# quad_exp_vca_pnl.net
KiCad netlist of a schematic drawn in EAGLE
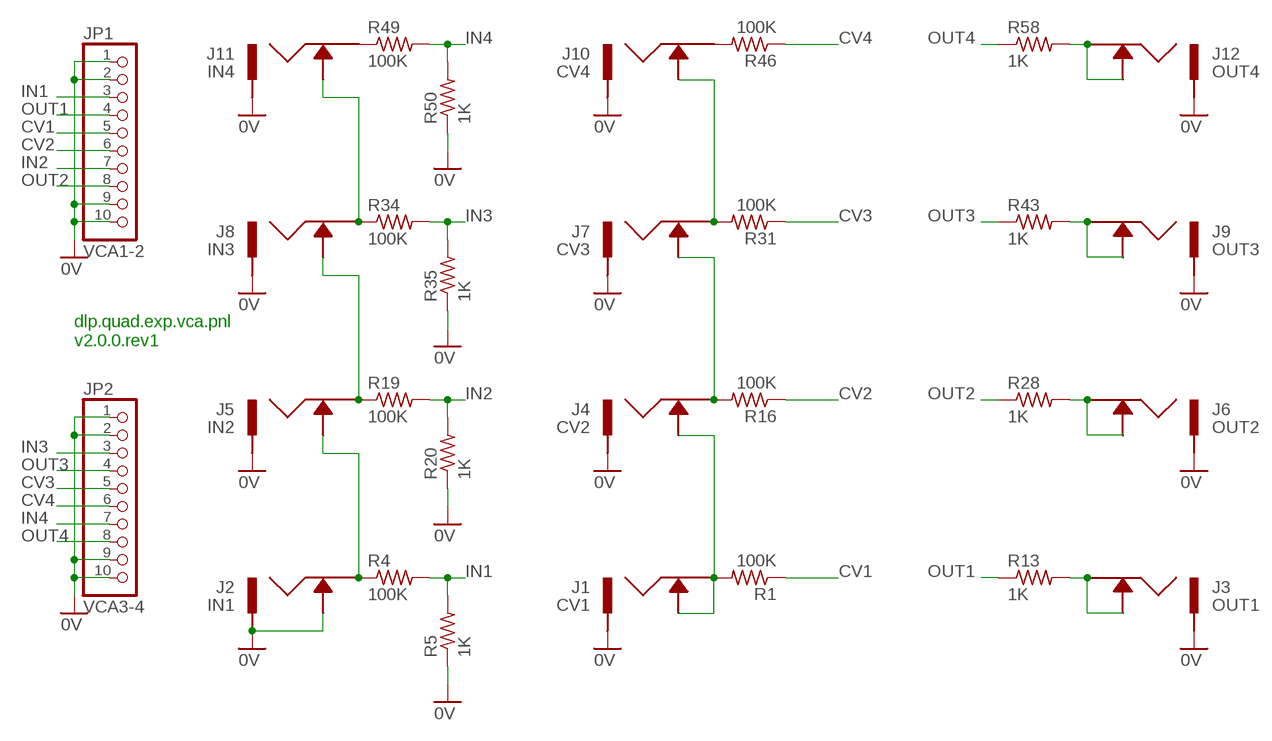
[diagram p0: schematic, sheet 1]

(export (version "E")
  (design (tool "Eeschema 10.0.6"))
  (components
    (comp (ref "J1")
      (value "CV1")
      (footprint "eagle-import:ACJM-MV35-2S")
      (libsource (lib "eagle-import") (part "ACJM-MV35-2S"))
    )
    (comp (ref "J2")
      (value "IN1")
      (footprint "eagle-import:ACJM-MV35-2S")
      (libsource (lib "eagle-import") (part "ACJM-MV35-2S"))
    )
    (comp (ref "J3")
      (value "OUT1")
      (footprint "eagle-import:ACJM-MV35-2S")
      (libsource (lib "eagle-import") (part "ACJM-MV35-2S"))
    )
    (comp (ref "J4")
      (value "CV2")
      (footprint "eagle-import:ACJM-MV35-2S")
      (libsource (lib "eagle-import") (part "ACJM-MV35-2S"))
    )
    (comp (ref "J5")
      (value "IN2")
      (footprint "eagle-import:ACJM-MV35-2S")
      (libsource (lib "eagle-import") (part "ACJM-MV35-2S"))
    )
    (comp (ref "J6")
      (value "OUT2")
      (footprint "eagle-import:ACJM-MV35-2S")
      (libsource (lib "eagle-import") (part "ACJM-MV35-2S"))
    )
    (comp (ref "J7")
      (value "CV3")
      (footprint "eagle-import:ACJM-MV35-2S")
      (libsource (lib "eagle-import") (part "ACJM-MV35-2S"))
    )
    (comp (ref "J8")
      (value "IN3")
      (footprint "eagle-import:ACJM-MV35-2S")
      (libsource (lib "eagle-import") (part "ACJM-MV35-2S"))
    )
    (comp (ref "J9")
      (value "OUT3")
      (footprint "eagle-import:ACJM-MV35-2S")
      (libsource (lib "eagle-import") (part "ACJM-MV35-2S"))
    )
    (comp (ref "J10")
      (value "CV4")
      (footprint "eagle-import:ACJM-MV35-2S")
      (libsource (lib "eagle-import") (part "ACJM-MV35-2S"))
    )
    (comp (ref "J11")
      (value "IN4")
      (footprint "eagle-import:ACJM-MV35-2S")
      (libsource (lib "eagle-import") (part "ACJM-MV35-2S"))
    )
    (comp (ref "J12")
      (value "OUT4")
      (footprint "eagle-import:ACJM-MV35-2S")
      (libsource (lib "eagle-import") (part "ACJM-MV35-2S"))
    )
    (comp (ref "JP1")
      (value "VCA1-2")
      (footprint "eagle-import:1X10")
      (libsource (lib "eagle-import") (part "PINHD-1X10"))
    )
    (comp (ref "JP2")
      (value "VCA3-4")
      (footprint "eagle-import:1X10")
      (libsource (lib "eagle-import") (part "PINHD-1X10"))
    )
    (comp (ref "R1")
      (value "100K")
      (footprint "eagle-import:0207_7")
      (libsource (lib "eagle-import") (part "R-US_0207/7"))
    )
    (comp (ref "R4")
      (value "100K")
      (footprint "eagle-import:0207_7")
      (libsource (lib "eagle-import") (part "R-US_0207/7"))
    )
    (comp (ref "R5")
      (value "1K")
      (footprint "eagle-import:0207_7")
      (libsource (lib "eagle-import") (part "R-US_0207/7"))
    )
    (comp (ref "R13")
      (value "1K")
      (footprint "eagle-import:0207_7")
      (libsource (lib "eagle-import") (part "R-US_0207/7"))
    )
    (comp (ref "R16")
      (value "100K")
      (footprint "eagle-import:0207_7")
      (libsource (lib "eagle-import") (part "R-US_0207/7"))
    )
    (comp (ref "R19")
      (value "100K")
      (footprint "eagle-import:0207_7")
      (libsource (lib "eagle-import") (part "R-US_0207/7"))
    )
    (comp (ref "R20")
      (value "1K")
      (footprint "eagle-import:0207_7")
      (libsource (lib "eagle-import") (part "R-US_0207/7"))
    )
    (comp (ref "R28")
      (value "1K")
      (footprint "eagle-import:0207_7")
      (libsource (lib "eagle-import") (part "R-US_0207/7"))
    )
    (comp (ref "R31")
      (value "100K")
      (footprint "eagle-import:0207_7")
      (libsource (lib "eagle-import") (part "R-US_0207/7"))
    )
    (comp (ref "R34")
      (value "100K")
      (footprint "eagle-import:0207_7")
      (libsource (lib "eagle-import") (part "R-US_0207/7"))
    )
    (comp (ref "R35")
      (value "1K")
      (footprint "eagle-import:0207_7")
      (libsource (lib "eagle-import") (part "R-US_0207/7"))
    )
    (comp (ref "R43")
      (value "1K")
      (footprint "eagle-import:0207_7")
      (libsource (lib "eagle-import") (part "R-US_0207/7"))
    )
    (comp (ref "R46")
      (value "100K")
      (footprint "eagle-import:0207_7")
      (libsource (lib "eagle-import") (part "R-US_0207/7"))
    )
    (comp (ref "R49")
      (value "100K")
      (footprint "eagle-import:0207_7")
      (libsource (lib "eagle-import") (part "R-US_0207/7"))
    )
    (comp (ref "R50")
      (value "1K")
      (footprint "eagle-import:0207_7")
      (libsource (lib "eagle-import") (part "R-US_0207/7"))
    )
    (comp (ref "R58")
      (value "1K")
      (footprint "eagle-import:0207_7")
      (libsource (lib "eagle-import") (part "R-US_0207/7"))
    )
  )
  (nets
    (net (code "1") (name "/CV1") (class "Default")
      (node (ref "JP1") (pin "5") (pinfunction "5_5") (pintype "passive"))
      (node (ref "R1") (pin "1") (pinfunction "1_1") (pintype "passive"))
    )
    (net (code "2") (name "/CV2") (class "Default")
      (node (ref "JP1") (pin "6") (pinfunction "6_6") (pintype "passive"))
      (node (ref "R16") (pin "1") (pinfunction "1_1") (pintype "passive"))
    )
    (net (code "3") (name "/CV3") (class "Default")
      (node (ref "JP2") (pin "5") (pinfunction "5_5") (pintype "passive"))
      (node (ref "R31") (pin "1") (pinfunction "1_1") (pintype "passive"))
    )
    (net (code "4") (name "/CV4") (class "Default")
      (node (ref "JP2") (pin "6") (pinfunction "6_6") (pintype "passive"))
      (node (ref "R46") (pin "1") (pinfunction "1_1") (pintype "passive"))
    )
    (net (code "5") (name "/IN1") (class "Default")
      (node (ref "JP1") (pin "3") (pinfunction "3_3") (pintype "passive"))
      (node (ref "R4") (pin "2") (pinfunction "2_2") (pintype "passive"))
      (node (ref "R5") (pin "2") (pinfunction "2_2") (pintype "passive"))
    )
    (net (code "6") (name "/IN2") (class "Default")
      (node (ref "JP1") (pin "7") (pinfunction "7_7") (pintype "passive"))
      (node (ref "R19") (pin "2") (pinfunction "2_2") (pintype "passive"))
      (node (ref "R20") (pin "2") (pinfunction "2_2") (pintype "passive"))
    )
    (net (code "7") (name "/IN3") (class "Default")
      (node (ref "JP2") (pin "3") (pinfunction "3_3") (pintype "passive"))
      (node (ref "R34") (pin "2") (pinfunction "2_2") (pintype "passive"))
      (node (ref "R35") (pin "2") (pinfunction "2_2") (pintype "passive"))
    )
    (net (code "8") (name "/IN4") (class "Default")
      (node (ref "JP2") (pin "7") (pinfunction "7_7") (pintype "passive"))
      (node (ref "R49") (pin "2") (pinfunction "2_2") (pintype "passive"))
      (node (ref "R50") (pin "2") (pinfunction "2_2") (pintype "passive"))
    )
    (net (code "9") (name "/OUT1") (class "Default")
      (node (ref "JP1") (pin "4") (pinfunction "4_4") (pintype "passive"))
      (node (ref "R13") (pin "1") (pinfunction "1_1") (pintype "passive"))
    )
    (net (code "10") (name "/OUT2") (class "Default")
      (node (ref "JP1") (pin "8") (pinfunction "8_8") (pintype "passive"))
      (node (ref "R28") (pin "1") (pinfunction "1_1") (pintype "passive"))
    )
    (net (code "11") (name "/OUT3") (class "Default")
      (node (ref "JP2") (pin "4") (pinfunction "4_4") (pintype "passive"))
      (node (ref "R43") (pin "1") (pinfunction "1_1") (pintype "passive"))
    )
    (net (code "12") (name "/OUT4") (class "Default")
      (node (ref "JP2") (pin "8") (pinfunction "8_8") (pintype "passive"))
      (node (ref "R58") (pin "1") (pinfunction "1_1") (pintype "passive"))
    )
    (net (code "13") (name "0V") (class "Default")
      (node (ref "J1") (pin "P$1") (pinfunction "P$1_P$1") (pintype "bidirectional"))
      (node (ref "J10") (pin "P$1") (pinfunction "P$1_P$1") (pintype "bidirectional"))
      (node (ref "J11") (pin "P$1") (pinfunction "P$1_P$1") (pintype "bidirectional"))
      (node (ref "J12") (pin "P$1") (pinfunction "P$1_P$1") (pintype "bidirectional"))
      (node (ref "J2") (pin "P$1") (pinfunction "P$1_P$1") (pintype "bidirectional"))
      (node (ref "J2") (pin "P$2") (pinfunction "P$3_P$2") (pintype "bidirectional"))
      (node (ref "J3") (pin "P$1") (pinfunction "P$1_P$1") (pintype "bidirectional"))
      (node (ref "J4") (pin "P$1") (pinfunction "P$1_P$1") (pintype "bidirectional"))
      (node (ref "J5") (pin "P$1") (pinfunction "P$1_P$1") (pintype "bidirectional"))
      (node (ref "J6") (pin "P$1") (pinfunction "P$1_P$1") (pintype "bidirectional"))
      (node (ref "J7") (pin "P$1") (pinfunction "P$1_P$1") (pintype "bidirectional"))
      (node (ref "J8") (pin "P$1") (pinfunction "P$1_P$1") (pintype "bidirectional"))
      (node (ref "J9") (pin "P$1") (pinfunction "P$1_P$1") (pintype "bidirectional"))
      (node (ref "JP1") (pin "1") (pinfunction "1_1") (pintype "passive"))
      (node (ref "JP1") (pin "10") (pinfunction "10_10") (pintype "passive"))
      (node (ref "JP1") (pin "2") (pinfunction "2_2") (pintype "passive"))
      (node (ref "JP1") (pin "9") (pinfunction "9_9") (pintype "passive"))
      (node (ref "JP2") (pin "1") (pinfunction "1_1") (pintype "passive"))
      (node (ref "JP2") (pin "10") (pinfunction "10_10") (pintype "passive"))
      (node (ref "JP2") (pin "2") (pinfunction "2_2") (pintype "passive"))
      (node (ref "JP2") (pin "9") (pinfunction "9_9") (pintype "passive"))
      (node (ref "R20") (pin "1") (pinfunction "1_1") (pintype "passive"))
      (node (ref "R35") (pin "1") (pinfunction "1_1") (pintype "passive"))
      (node (ref "R5") (pin "1") (pinfunction "1_1") (pintype "passive"))
      (node (ref "R50") (pin "1") (pinfunction "1_1") (pintype "passive"))
    )
    (net (code "14") (name "Net-(J1-P$2)") (class "Default")
      (node (ref "J1") (pin "P$2") (pinfunction "P$3_P$2") (pintype "bidirectional"))
      (node (ref "J1") (pin "P$3") (pinfunction "P$2_P$3") (pintype "bidirectional"))
      (node (ref "J4") (pin "P$2") (pinfunction "P$3_P$2") (pintype "bidirectional"))
      (node (ref "R1") (pin "2") (pinfunction "2_2") (pintype "passive"))
    )
    (net (code "15") (name "Net-(J2-P$2)") (class "Default")
      (node (ref "J2") (pin "P$3") (pinfunction "P$2_P$3") (pintype "bidirectional"))
      (node (ref "J5") (pin "P$2") (pinfunction "P$3_P$2") (pintype "bidirectional"))
      (node (ref "R4") (pin "1") (pinfunction "1_1") (pintype "passive"))
    )
    (net (code "16") (name "Net-(J3-P$2)") (class "Default")
      (node (ref "J3") (pin "P$2") (pinfunction "P$3_P$2") (pintype "bidirectional"))
      (node (ref "J3") (pin "P$3") (pinfunction "P$2_P$3") (pintype "bidirectional"))
      (node (ref "R13") (pin "2") (pinfunction "2_2") (pintype "passive"))
    )
    (net (code "17") (name "Net-(J4-P$2)") (class "Default")
      (node (ref "J4") (pin "P$3") (pinfunction "P$2_P$3") (pintype "bidirectional"))
      (node (ref "J7") (pin "P$2") (pinfunction "P$3_P$2") (pintype "bidirectional"))
      (node (ref "R16") (pin "2") (pinfunction "2_2") (pintype "passive"))
    )
    (net (code "18") (name "Net-(J5-P$2)") (class "Default")
      (node (ref "J5") (pin "P$3") (pinfunction "P$2_P$3") (pintype "bidirectional"))
      (node (ref "J8") (pin "P$2") (pinfunction "P$3_P$2") (pintype "bidirectional"))
      (node (ref "R19") (pin "1") (pinfunction "1_1") (pintype "passive"))
    )
    (net (code "19") (name "Net-(J6-P$2)") (class "Default")
      (node (ref "J6") (pin "P$2") (pinfunction "P$3_P$2") (pintype "bidirectional"))
      (node (ref "J6") (pin "P$3") (pinfunction "P$2_P$3") (pintype "bidirectional"))
      (node (ref "R28") (pin "2") (pinfunction "2_2") (pintype "passive"))
    )
    (net (code "20") (name "Net-(J9-P$2)") (class "Default")
      (node (ref "J9") (pin "P$2") (pinfunction "P$3_P$2") (pintype "bidirectional"))
      (node (ref "J9") (pin "P$3") (pinfunction "P$2_P$3") (pintype "bidirectional"))
      (node (ref "R43") (pin "2") (pinfunction "2_2") (pintype "passive"))
    )
    (net (code "21") (name "Net-(J10-P$2)") (class "Default")
      (node (ref "J10") (pin "P$3") (pinfunction "P$2_P$3") (pintype "bidirectional"))
      (node (ref "R46") (pin "2") (pinfunction "2_2") (pintype "passive"))
    )
    (net (code "22") (name "Net-(J10-P$3)") (class "Default")
      (node (ref "J10") (pin "P$2") (pinfunction "P$3_P$2") (pintype "bidirectional"))
      (node (ref "J7") (pin "P$3") (pinfunction "P$2_P$3") (pintype "bidirectional"))
      (node (ref "R31") (pin "2") (pinfunction "2_2") (pintype "passive"))
    )
    (net (code "23") (name "Net-(J11-P$2)") (class "Default")
      (node (ref "J11") (pin "P$3") (pinfunction "P$2_P$3") (pintype "bidirectional"))
      (node (ref "R49") (pin "1") (pinfunction "1_1") (pintype "passive"))
    )
    (net (code "24") (name "Net-(J11-P$3)") (class "Default")
      (node (ref "J11") (pin "P$2") (pinfunction "P$3_P$2") (pintype "bidirectional"))
      (node (ref "J8") (pin "P$3") (pinfunction "P$2_P$3") (pintype "bidirectional"))
      (node (ref "R34") (pin "1") (pinfunction "1_1") (pintype "passive"))
    )
    (net (code "25") (name "Net-(J12-P$2)") (class "Default")
      (node (ref "J12") (pin "P$2") (pinfunction "P$3_P$2") (pintype "bidirectional"))
      (node (ref "J12") (pin "P$3") (pinfunction "P$2_P$3") (pintype "bidirectional"))
      (node (ref "R58") (pin "2") (pinfunction "2_2") (pintype "passive"))
    )
  )
)
